# ESP32.net
KiCad netlist of a schematic drawn in Altium Designer
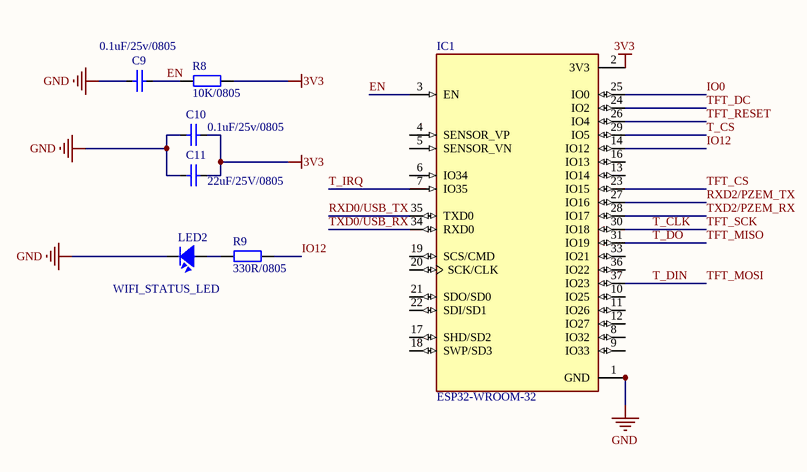
[diagram p0: ESP32.SchDoc]

(export (version "E")
  (design (tool "Eeschema 10.0.6"))
  (components
    (comp (ref "C9")
      (value "0.1uF/25v/0805")
      (footprint "CAP_0805")
      (description "Capacitor")
      (fields (field (name "PUBLISHER") "Altium Limited"))
      (libsource (lib "My Library") (part "CapSMD"))
    )
    (comp (ref "C10")
      (value "0.1uF/25v/0805")
      (footprint "CAP_0805")
      (description "Capacitor")
      (fields (field (name "PUBLISHER") "Altium Limited"))
      (libsource (lib "My Library") (part "CapSMD"))
    )
    (comp (ref "C11")
      (value "22uF/25V/0805")
      (footprint "CAP_0805")
      (description "Capacitor")
      (fields (field (name "PUBLISHER") "Altium Limited"))
      (libsource (lib "My Library") (part "CapSMD"))
    )
    (comp (ref "IC1")
      (value "ESP32-WROOM-32")
      (footprint "MODULE_ESP32-WROOM-32")
      (description "Bluetooth, WiFi Transceiver Module 2.4GHz ~ 2.5GHz Surface Mount")
      (fields (field (name "MF") "Espressif Systems") (field (name "DIGI-KEY_PART_NUMBER") "1904-1010-1-ND"))
      (libsource (lib "My Library") (part "ESP32-WROOM-32"))
    )
    (comp (ref "LED2")
      (value "WIFI_STATUS_LED")
      (footprint "LED-3")
      (description "LED Single colour Green and Red")
      (libsource (lib "My Library") (part "LED"))
    )
    (comp (ref "R8")
      (value "10K/0805")
      (footprint "RES-SMD-0805")
      (description "Resistor SMD")
      (fields
        (field (name "MANUFACTURER") "Generic Components")
        (field (name "PUBLISHER") "Altium Hobart Technology Centre")
      )
      (libsource (lib "My Library") (part "Resistor - SMD"))
    )
    (comp (ref "R9")
      (value "330R/0805")
      (footprint "RES-SMD-0101")
      (description "Resistor SMD")
      (fields
        (field (name "MANUFACTURER") "Generic Components")
        (field (name "PUBLISHER") "Altium Hobart Technology Centre")
      )
      (libsource (lib "My Library") (part "Resistor - SMD"))
    )
  )
  (nets
    (net (code "1") (name "/EN") (class "Default")
      (node (ref "C9") (pin "2") (pinfunction "2_2") (pintype "passive"))
      (node (ref "IC1") (pin "3") (pinfunction "EN_3") (pintype "input"))
      (node (ref "R8") (pin "1") (pinfunction "1_1") (pintype "passive"))
    )
    (net (code "2") (name "/IO0") (class "Default")
      (node (ref "IC1") (pin "25") (pinfunction "IO0_25") (pintype "bidirectional"))
    )
    (net (code "3") (name "/IO12") (class "Default")
      (node (ref "IC1") (pin "14") (pinfunction "IO12_14") (pintype "bidirectional"))
      (node (ref "R9") (pin "1") (pinfunction "1_1") (pintype "passive"))
    )
    (net (code "4") (name "/RXD0{slash}USB_TX") (class "Default")
      (node (ref "IC1") (pin "35") (pinfunction "TXD0_35") (pintype "bidirectional"))
    )
    (net (code "5") (name "/RXD2{slash}PZEM_TX") (class "Default")
      (node (ref "IC1") (pin "27") (pinfunction "IO16_27") (pintype "bidirectional"))
    )
    (net (code "6") (name "/TFT_CS") (class "Default")
      (node (ref "IC1") (pin "23") (pinfunction "IO15_23") (pintype "bidirectional"))
    )
    (net (code "7") (name "/TFT_DC") (class "Default")
      (node (ref "IC1") (pin "24") (pinfunction "IO2_24") (pintype "bidirectional"))
    )
    (net (code "8") (name "/TFT_MISO") (class "Default")
      (node (ref "IC1") (pin "31") (pinfunction "IO19_31") (pintype "bidirectional"))
    )
    (net (code "9") (name "/TFT_MOSI") (class "Default")
      (node (ref "IC1") (pin "37") (pinfunction "IO23_37") (pintype "bidirectional"))
    )
    (net (code "10") (name "/TFT_RESET") (class "Default")
      (node (ref "IC1") (pin "26") (pinfunction "IO4_26") (pintype "bidirectional"))
    )
    (net (code "11") (name "/TFT_SCK") (class "Default")
      (node (ref "IC1") (pin "30") (pinfunction "IO18_30") (pintype "bidirectional"))
    )
    (net (code "12") (name "/TXD0{slash}USB_RX") (class "Default")
      (node (ref "IC1") (pin "34") (pinfunction "RXD0_34") (pintype "bidirectional"))
    )
    (net (code "13") (name "/TXD2{slash}PZEM_RX") (class "Default")
      (node (ref "IC1") (pin "28") (pinfunction "IO17_28") (pintype "bidirectional"))
    )
    (net (code "14") (name "/T_CS") (class "Default")
      (node (ref "IC1") (pin "29") (pinfunction "IO5_29") (pintype "bidirectional"))
    )
    (net (code "15") (name "/T_IRQ") (class "Default")
      (node (ref "IC1") (pin "7") (pinfunction "IO35_7") (pintype "input"))
    )
    (net (code "16") (name "3V3") (class "Default")
      (node (ref "C10") (pin "2") (pinfunction "2_2") (pintype "passive"))
      (node (ref "C11") (pin "2") (pinfunction "2_2") (pintype "passive"))
      (node (ref "IC1") (pin "2") (pinfunction "3V3_2") (pintype "power_in"))
      (node (ref "R8") (pin "2") (pinfunction "2_2") (pintype "passive"))
    )
    (net (code "17") (name "GND") (class "Default")
      (node (ref "C10") (pin "1") (pinfunction "1_1") (pintype "passive"))
      (node (ref "C11") (pin "1") (pinfunction "1_1") (pintype "passive"))
      (node (ref "C9") (pin "1") (pinfunction "1_1") (pintype "passive"))
      (node (ref "IC1") (pin "1") (pinfunction "GND_1") (pintype "power_in"))
      (node (ref "IC1") (pin "15") (pinfunction "GND_15") (pintype "power_in"))
      (node (ref "IC1") (pin "38") (pinfunction "GND_38") (pintype "power_in"))
      (node (ref "IC1") (pin "39_1") (pinfunction "GND_39_1") (pintype "power_in"))
      (node (ref "IC1") (pin "39_10") (pinfunction "GND_39_10") (pintype "power_in"))
      (node (ref "IC1") (pin "39_11") (pinfunction "GND_39_11") (pintype "power_in"))
      (node (ref "IC1") (pin "39_12") (pinfunction "GND_39_12") (pintype "power_in"))
      (node (ref "IC1") (pin "39_13") (pinfunction "GND_39_13") (pintype "power_in"))
      (node (ref "IC1") (pin "39_14") (pinfunction "GND_39_14") (pintype "power_in"))
      (node (ref "IC1") (pin "39_15") (pinfunction "GND_39_15") (pintype "power_in"))
      (node (ref "IC1") (pin "39_16") (pinfunction "GND_39_16") (pintype "power_in"))
      (node (ref "IC1") (pin "39_17") (pinfunction "GND_39_17") (pintype "power_in"))
      (node (ref "IC1") (pin "39_18") (pinfunction "GND_39_18") (pintype "power_in"))
      (node (ref "IC1") (pin "39_19") (pinfunction "GND_39_19") (pintype "power_in"))
      (node (ref "IC1") (pin "39_2") (pinfunction "GND_39_2") (pintype "power_in"))
      (node (ref "IC1") (pin "39_20") (pinfunction "GND_39_20") (pintype "power_in"))
      (node (ref "IC1") (pin "39_21") (pinfunction "GND_39_21") (pintype "power_in"))
      (node (ref "IC1") (pin "39_3") (pinfunction "GND_39_3") (pintype "power_in"))
      (node (ref "IC1") (pin "39_4") (pinfunction "GND_39_4") (pintype "power_in"))
      (node (ref "IC1") (pin "39_5") (pinfunction "GND_39_5") (pintype "power_in"))
      (node (ref "IC1") (pin "39_6") (pinfunction "GND_39_6") (pintype "power_in"))
      (node (ref "IC1") (pin "39_7") (pinfunction "GND_39_7") (pintype "power_in"))
      (node (ref "IC1") (pin "39_8") (pinfunction "GND_39_8") (pintype "power_in"))
      (node (ref "IC1") (pin "39_9") (pinfunction "GND_39_9") (pintype "power_in"))
      (node (ref "LED2") (pin "2") (pinfunction "2_2") (pintype "passive"))
    )
    (net (code "18") (name "Net-(LED2-Pad1)") (class "Default")
      (node (ref "LED2") (pin "1") (pinfunction "1_1") (pintype "passive"))
      (node (ref "R9") (pin "2") (pinfunction "2_2") (pintype "passive"))
    )
    (net (code "19") (name "unconnected-(IC1-IO13-Pad16)") (class "Default")
      (node (ref "IC1") (pin "16") (pinfunction "IO13_16") (pintype "bidirectional"))
    )
    (net (code "20") (name "unconnected-(IC1-IO14-Pad13)") (class "Default")
      (node (ref "IC1") (pin "13") (pinfunction "IO14_13") (pintype "bidirectional"))
    )
    (net (code "21") (name "unconnected-(IC1-IO21-Pad33)") (class "Default")
      (node (ref "IC1") (pin "33") (pinfunction "IO21_33") (pintype "bidirectional"))
    )
    (net (code "22") (name "unconnected-(IC1-IO22-Pad36)") (class "Default")
      (node (ref "IC1") (pin "36") (pinfunction "IO22_36") (pintype "bidirectional"))
    )
    (net (code "23") (name "unconnected-(IC1-IO25-Pad10)") (class "Default")
      (node (ref "IC1") (pin "10") (pinfunction "IO25_10") (pintype "bidirectional"))
    )
    (net (code "24") (name "unconnected-(IC1-IO26-Pad11)") (class "Default")
      (node (ref "IC1") (pin "11") (pinfunction "IO26_11") (pintype "bidirectional"))
    )
    (net (code "25") (name "unconnected-(IC1-IO27-Pad12)") (class "Default")
      (node (ref "IC1") (pin "12") (pinfunction "IO27_12") (pintype "bidirectional"))
    )
    (net (code "26") (name "unconnected-(IC1-IO32-Pad8)") (class "Default")
      (node (ref "IC1") (pin "8") (pinfunction "IO32_8") (pintype "bidirectional"))
    )
    (net (code "27") (name "unconnected-(IC1-IO33-Pad9)") (class "Default")
      (node (ref "IC1") (pin "9") (pinfunction "IO33_9") (pintype "bidirectional"))
    )
    (net (code "28") (name "unconnected-(IC1-IO34-Pad6)") (class "Default")
      (node (ref "IC1") (pin "6") (pinfunction "IO34_6") (pintype "input"))
    )
    (net (code "29") (name "unconnected-(IC1-SCK{slash}CLK-Pad20)") (class "Default")
      (node (ref "IC1") (pin "20") (pinfunction "SCK/CLK_20") (pintype "bidirectional"))
    )
    (net (code "30") (name "unconnected-(IC1-SCS{slash}CMD-Pad19)") (class "Default")
      (node (ref "IC1") (pin "19") (pinfunction "SCS/CMD_19") (pintype "bidirectional"))
    )
    (net (code "31") (name "unconnected-(IC1-SDI{slash}SD1-Pad22)") (class "Default")
      (node (ref "IC1") (pin "22") (pinfunction "SDI/SD1_22") (pintype "bidirectional"))
    )
    (net (code "32") (name "unconnected-(IC1-SDO{slash}SD0-Pad21)") (class "Default")
      (node (ref "IC1") (pin "21") (pinfunction "SDO/SD0_21") (pintype "bidirectional"))
    )
    (net (code "33") (name "unconnected-(IC1-SENSOR_VN-Pad5)") (class "Default")
      (node (ref "IC1") (pin "5") (pinfunction "SENSOR_VN_5") (pintype "input"))
    )
    (net (code "34") (name "unconnected-(IC1-SENSOR_VP-Pad4)") (class "Default")
      (node (ref "IC1") (pin "4") (pinfunction "SENSOR_VP_4") (pintype "input"))
    )
    (net (code "35") (name "unconnected-(IC1-SHD{slash}SD2-Pad17)") (class "Default")
      (node (ref "IC1") (pin "17") (pinfunction "SHD/SD2_17") (pintype "bidirectional"))
    )
    (net (code "36") (name "unconnected-(IC1-SWP{slash}SD3-Pad18)") (class "Default")
      (node (ref "IC1") (pin "18") (pinfunction "SWP/SD3_18") (pintype "bidirectional"))
    )
  )
)
